# 12V_UPS2.net
KiCad netlist of a schematic drawn in EAGLE
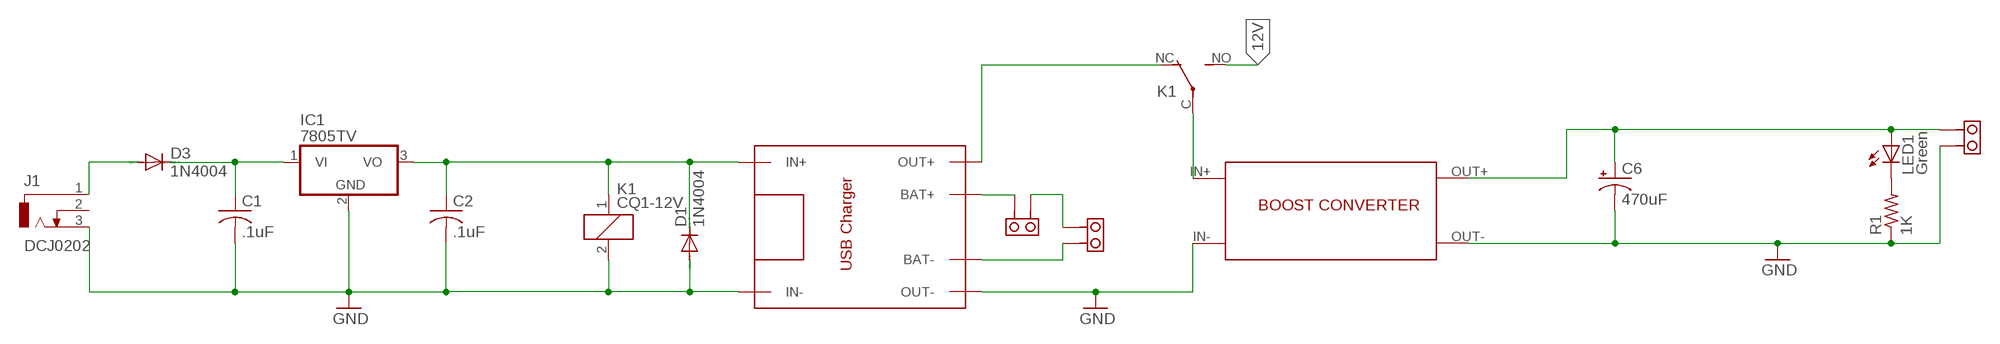
[diagram p0: schematic, sheet 1]

(export (version "E")
  (design (tool "Eeschema 10.0.6"))
  (components
    (comp (ref "C1")
      (value ".1uF")
      (footprint "eagle-import:C025-030X050")
      (libsource (lib "eagle-import") (part "C-US025-030X050"))
    )
    (comp (ref "C2")
      (value ".1uF")
      (footprint "eagle-import:C025-030X050")
      (libsource (lib "eagle-import") (part "C-US025-030X050"))
    )
    (comp (ref "C6")
      (value "470uF")
      (footprint "eagle-import:E5-8,5")
      (libsource (lib "eagle-import") (part "CPOL-USE5-8.5"))
    )
    (comp (ref "D1")
      (value "1N4004")
      (footprint "eagle-import:DO41-10")
      (libsource (lib "eagle-import") (part "1N4004"))
    )
    (comp (ref "D3")
      (value "1N4004")
      (footprint "eagle-import:DO41-10")
      (libsource (lib "eagle-import") (part "1N4004"))
    )
    (comp (ref "IC1")
      (value "7805TV")
      (footprint "eagle-import:TO220V")
      (libsource (lib "eagle-import") (part "78TV05"))
    )
    (comp (ref "J1")
      (value "DCJ0202")
      (footprint "eagle-import:DCJ0202")
      (libsource (lib "eagle-import") (part "DCJ0202"))
    )
    (comp (ref "K1")
      (value "CQ1-12V")
      (footprint "eagle-import:CQ1")
      (libsource (lib "eagle-import") (part "CQ1-12V"))
    )
    (comp (ref "LED1")
      (value "Green")
      (footprint "eagle-import:LED5MM")
      (libsource (lib "eagle-import") (part "LED5MM"))
    )
    (comp (ref "R1")
      (value "1K")
      (footprint "eagle-import:0204V")
      (libsource (lib "eagle-import") (part "R-US_0204/2V"))
    )
    (comp (ref "U$1")
      (value "TP4056_TH")
      (footprint "eagle-import:TP4056_TH")
      (libsource (lib "eagle-import") (part "TP4056_TH"))
    )
    (comp (ref "U$2")
      (value "BOOST")
      (footprint "eagle-import:BOOST")
      (libsource (lib "eagle-import") (part "BOOST"))
    )
    (comp (ref "U$3")
      (value "BERG_2")
      (footprint "eagle-import:BERG_2")
      (libsource (lib "eagle-import") (part "BERG_2"))
    )
    (comp (ref "U$5")
      (value "BERG_2")
      (footprint "eagle-import:BERG_2")
      (libsource (lib "eagle-import") (part "BERG_2"))
    )
    (comp (ref "U$6")
      (value "BERG_2")
      (footprint "eagle-import:BERG_2")
      (libsource (lib "eagle-import") (part "BERG_2"))
    )
  )
  (nets
    (net (code "1") (name "12V") (class "Default")
      (node (ref "C1") (pin "1") (pinfunction "1_1") (pintype "passive"))
      (node (ref "D3") (pin "C") (pinfunction "C_C") (pintype "passive"))
      (node (ref "IC1") (pin "1") (pinfunction "VI_1") (pintype "input"))
      (node (ref "K1") (pin "NO") (pinfunction "S_NO") (pintype "passive"))
    )
    (net (code "2") (name "GND") (class "Default")
      (node (ref "C1") (pin "2") (pinfunction "2_2") (pintype "passive"))
      (node (ref "C2") (pin "2") (pinfunction "2_2") (pintype "passive"))
      (node (ref "C6") (pin "-") (pinfunction "-_-") (pintype "passive"))
      (node (ref "D1") (pin "A") (pinfunction "A_A") (pintype "passive"))
      (node (ref "IC1") (pin "2") (pinfunction "GND_2") (pintype "passive"))
      (node (ref "J1") (pin "3") (pinfunction "3_3") (pintype "passive"))
      (node (ref "K1") (pin "2") (pinfunction "2_2") (pintype "passive"))
      (node (ref "R1") (pin "1") (pinfunction "1_1") (pintype "passive"))
      (node (ref "U$1") (pin "IN-") (pinfunction "IN-_IN-") (pintype "bidirectional"))
      (node (ref "U$1") (pin "OUT-") (pinfunction "OUT-_OUT-") (pintype "bidirectional"))
      (node (ref "U$2") (pin "IN-") (pinfunction "IN-_IN-") (pintype "bidirectional"))
      (node (ref "U$2") (pin "OUT-") (pinfunction "OUT-_OUT-") (pintype "bidirectional"))
      (node (ref "U$3") (pin "E") (pinfunction "P$1_E") (pintype "bidirectional"))
    )
    (net (code "3") (name "Net-(D3-PadA)") (class "Default")
      (node (ref "D3") (pin "A") (pinfunction "A_A") (pintype "passive"))
      (node (ref "J1") (pin "1") (pinfunction "1_1") (pintype "passive"))
    )
    (net (code "4") (name "Net-(IC1-VO)") (class "Default")
      (node (ref "C2") (pin "1") (pinfunction "1_1") (pintype "passive"))
      (node (ref "D1") (pin "C") (pinfunction "C_C") (pintype "passive"))
      (node (ref "IC1") (pin "3") (pinfunction "VO_3") (pintype "passive"))
      (node (ref "K1") (pin "1") (pinfunction "1_1") (pintype "passive"))
      (node (ref "U$1") (pin "IN+") (pinfunction "IN+_IN+") (pintype "bidirectional"))
    )
    (net (code "5") (name "Net-(K1B-O)") (class "Default")
      (node (ref "K1") (pin "NC") (pinfunction "O_NC") (pintype "passive"))
      (node (ref "U$1") (pin "OUT+") (pinfunction "OUT+_OUT+") (pintype "bidirectional"))
    )
    (net (code "6") (name "Net-(K1B-P)") (class "Default")
      (node (ref "K1") (pin "C") (pinfunction "P_C") (pintype "passive"))
      (node (ref "U$2") (pin "IN+") (pinfunction "IN+_IN+") (pintype "bidirectional"))
    )
    (net (code "7") (name "Net-(LED1-C)") (class "Default")
      (node (ref "LED1") (pin "K") (pinfunction "C_K") (pintype "passive"))
      (node (ref "R1") (pin "2") (pinfunction "2_2") (pintype "passive"))
    )
    (net (code "8") (name "Net-(U$3-P$2)") (class "Default")
      (node (ref "C6") (pin "+") (pinfunction "+_+") (pintype "passive"))
      (node (ref "LED1") (pin "A") (pinfunction "A_A") (pintype "passive"))
      (node (ref "U$2") (pin "OUT+") (pinfunction "OUT+_OUT+") (pintype "bidirectional"))
      (node (ref "U$3") (pin "F") (pinfunction "P$2_F") (pintype "bidirectional"))
    )
    (net (code "9") (name "Net-(U$5-P$1)") (class "Default")
      (node (ref "U$1") (pin "BAT-") (pinfunction "BAT-_BAT-") (pintype "bidirectional"))
      (node (ref "U$5") (pin "E") (pinfunction "P$1_E") (pintype "bidirectional"))
    )
    (net (code "10") (name "Net-(U$5-P$2)") (class "Default")
      (node (ref "U$5") (pin "F") (pinfunction "P$2_F") (pintype "bidirectional"))
      (node (ref "U$6") (pin "F") (pinfunction "P$2_F") (pintype "bidirectional"))
    )
    (net (code "11") (name "Net-(U$6-P$1)") (class "Default")
      (node (ref "U$1") (pin "BAT+") (pinfunction "BAT+_BAT+") (pintype "bidirectional"))
      (node (ref "U$6") (pin "E") (pinfunction "P$1_E") (pintype "bidirectional"))
    )
    (net (code "12") (name "unconnected-(J1-Pad2)") (class "Default")
      (node (ref "J1") (pin "2") (pinfunction "2_2") (pintype "passive"))
    )
  )
)
